# Buzzer_Box.net
KiCad netlist of a schematic drawn in EAGLE
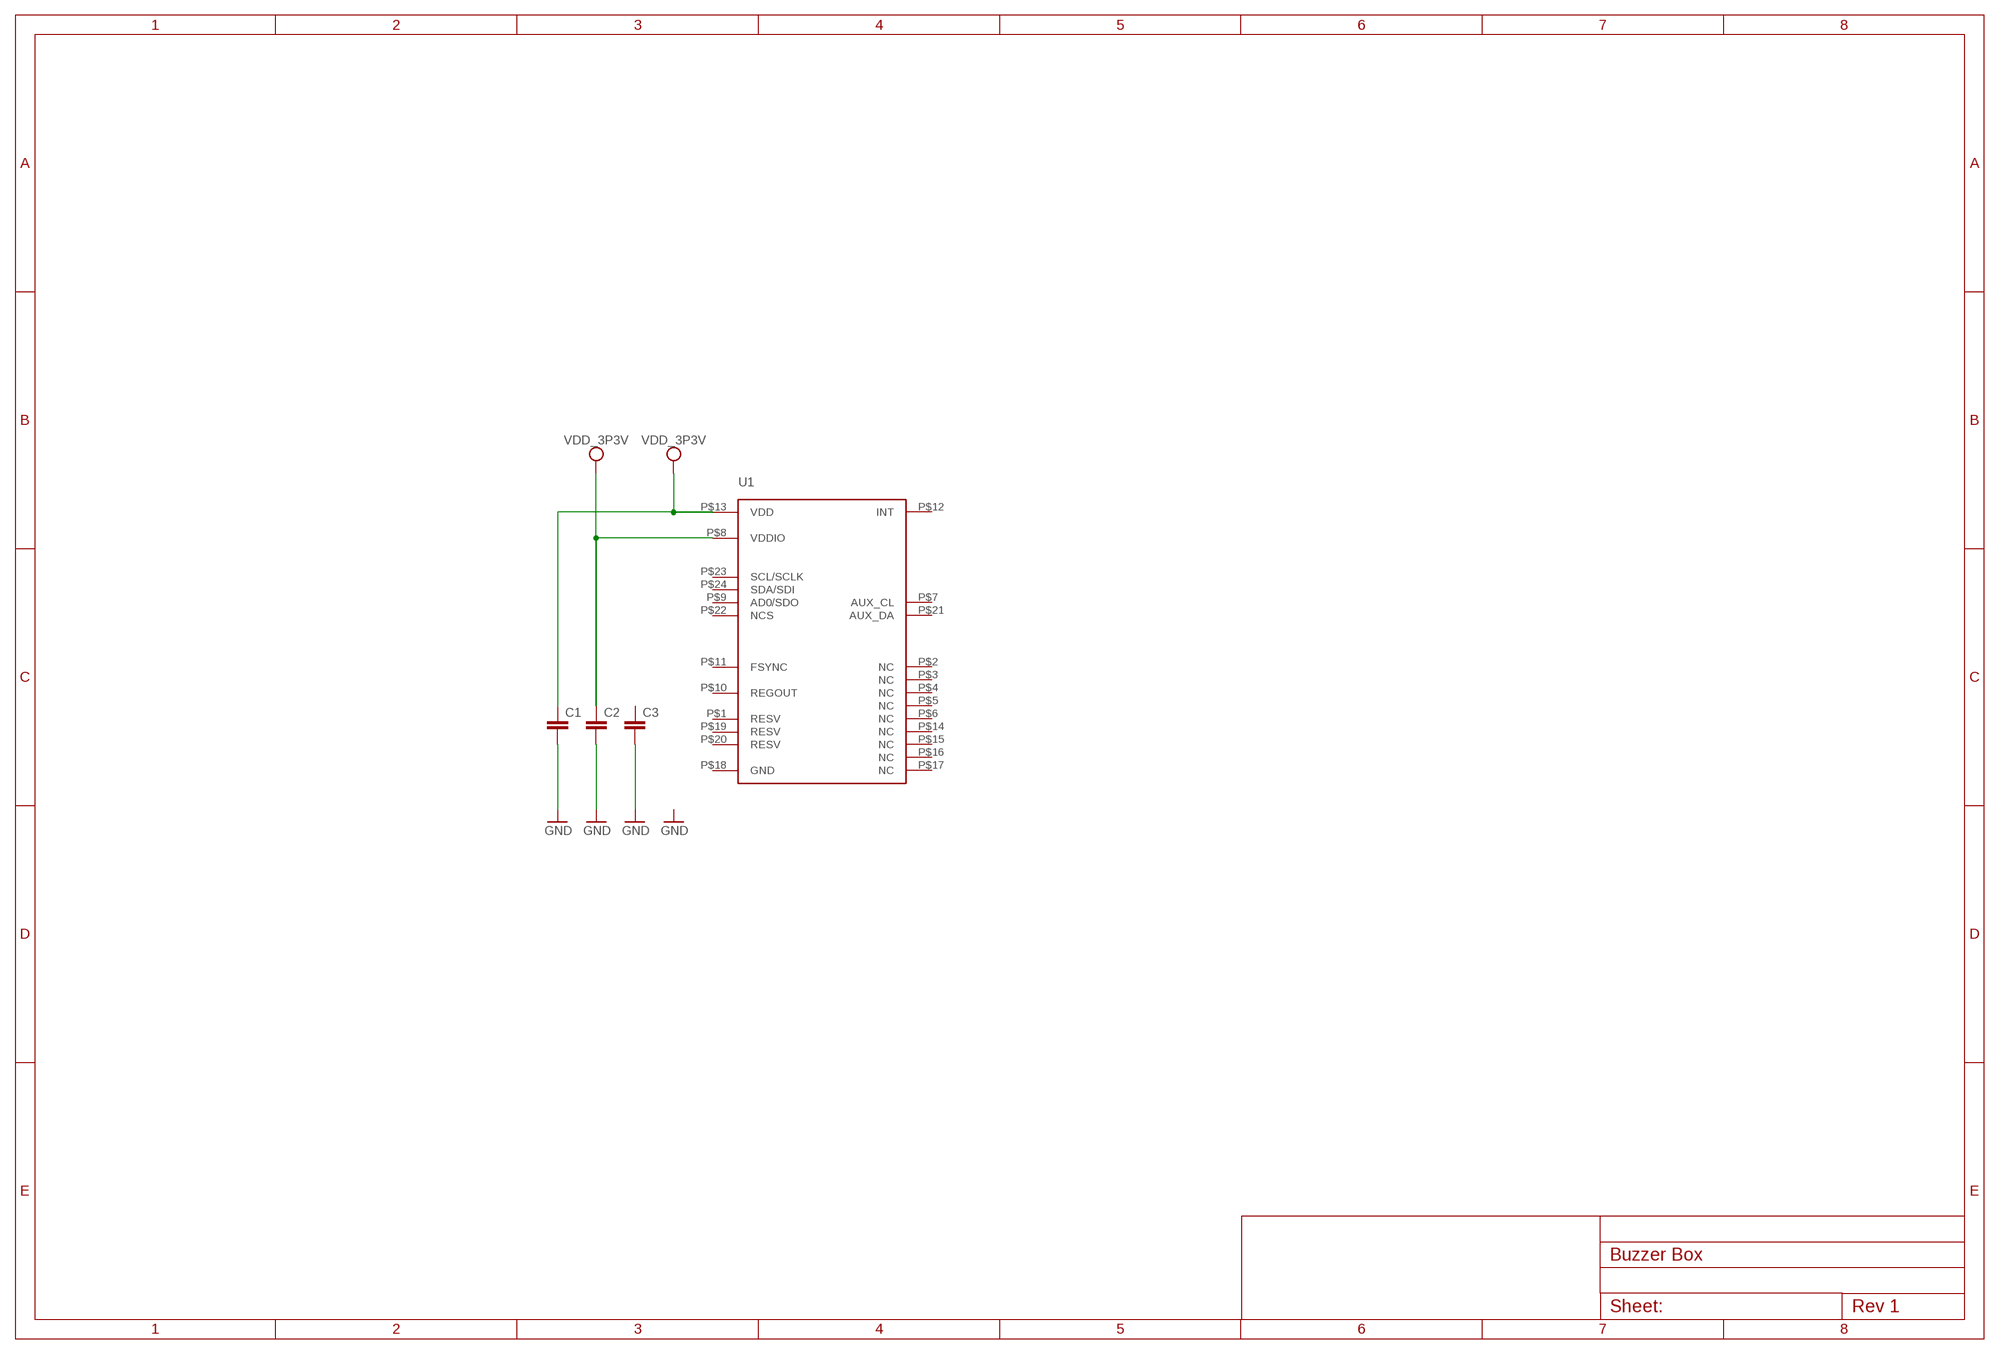
[diagram p0: schematic, sheet 1]

(export (version "E")
  (design (tool "Eeschema 10.0.6"))
  (components
    (comp (ref "C1")
      (value "C_C0402")
      (footprint "eagle-import:C0402")
      (libsource (lib "eagle-import") (part "C_C0402"))
    )
    (comp (ref "C2")
      (value "C_C0402")
      (footprint "eagle-import:C0402")
      (libsource (lib "eagle-import") (part "C_C0402"))
    )
    (comp (ref "C3")
      (value "C_C0402")
      (footprint "eagle-import:C0402")
      (libsource (lib "eagle-import") (part "C_C0402"))
    )
    (comp (ref "U1")
      (value "MPU-9250")
      (footprint "eagle-import:QFN-3X3MM")
      (libsource (lib "eagle-import") (part "MPU-9250"))
    )
  )
  (nets
    (net (code "1") (name "GND") (class "Default")
      (node (ref "C1") (pin "2") (pinfunction "2_2") (pintype "passive"))
      (node (ref "C2") (pin "2") (pinfunction "2_2") (pintype "passive"))
      (node (ref "C3") (pin "2") (pinfunction "2_2") (pintype "passive"))
    )
    (net (code "2") (name "VDD_3P3V") (class "Default")
      (node (ref "C1") (pin "1") (pinfunction "1_1") (pintype "passive"))
      (node (ref "C2") (pin "1") (pinfunction "1_1") (pintype "passive"))
      (node (ref "U1") (pin "P$13") (pinfunction "VDD_P$13") (pintype "bidirectional"))
      (node (ref "U1") (pin "P$8") (pinfunction "VDDIO_P$8") (pintype "bidirectional"))
    )
    (net (code "3") (name "unconnected-(C3-Pad1)") (class "Default")
      (node (ref "C3") (pin "1") (pinfunction "1_1") (pintype "passive"))
    )
    (net (code "4") (name "unconnected-(U1-AD0{slash}SDO-PadP$9)") (class "Default")
      (node (ref "U1") (pin "P$9") (pinfunction "AD0/SDO_P$9") (pintype "bidirectional"))
    )
    (net (code "5") (name "unconnected-(U1-AUX_CL-PadP$7)") (class "Default")
      (node (ref "U1") (pin "P$7") (pinfunction "AUX_CL_P$7") (pintype "bidirectional"))
    )
    (net (code "6") (name "unconnected-(U1-AUX_DA-PadP$21)") (class "Default")
      (node (ref "U1") (pin "P$21") (pinfunction "AUX_DA_P$21") (pintype "bidirectional"))
    )
    (net (code "7") (name "unconnected-(U1-FSYNC-PadP$11)") (class "Default")
      (node (ref "U1") (pin "P$11") (pinfunction "FSYNC_P$11") (pintype "bidirectional"))
    )
    (net (code "8") (name "unconnected-(U1-GND-PadP$18)") (class "Default")
      (node (ref "U1") (pin "P$18") (pinfunction "GND_P$18") (pintype "bidirectional"))
    )
    (net (code "9") (name "unconnected-(U1-INT-PadP$12)") (class "Default")
      (node (ref "U1") (pin "P$12") (pinfunction "INT_P$12") (pintype "bidirectional"))
    )
    (net (code "10") (name "unconnected-(U1-NC-PadP$2)") (class "Default")
      (node (ref "U1") (pin "P$2") (pinfunction "NC_P$2") (pintype "bidirectional"))
    )
    (net (code "11") (name "unconnected-(U1-NC-PadP$3)") (class "Default")
      (node (ref "U1") (pin "P$3") (pinfunction "NC_P$3") (pintype "bidirectional"))
    )
    (net (code "12") (name "unconnected-(U1-NC-PadP$4)") (class "Default")
      (node (ref "U1") (pin "P$4") (pinfunction "NC_P$4") (pintype "bidirectional"))
    )
    (net (code "13") (name "unconnected-(U1-NC-PadP$5)") (class "Default")
      (node (ref "U1") (pin "P$5") (pinfunction "NC_P$5") (pintype "bidirectional"))
    )
    (net (code "14") (name "unconnected-(U1-NC-PadP$6)") (class "Default")
      (node (ref "U1") (pin "P$6") (pinfunction "NC_P$6") (pintype "bidirectional"))
    )
    (net (code "15") (name "unconnected-(U1-NC-PadP$14)") (class "Default")
      (node (ref "U1") (pin "P$14") (pinfunction "NC_P$14") (pintype "bidirectional"))
    )
    (net (code "16") (name "unconnected-(U1-NC-PadP$15)") (class "Default")
      (node (ref "U1") (pin "P$15") (pinfunction "NC_P$15") (pintype "bidirectional"))
    )
    (net (code "17") (name "unconnected-(U1-NC-PadP$16)") (class "Default")
      (node (ref "U1") (pin "P$16") (pinfunction "NC_P$16") (pintype "bidirectional"))
    )
    (net (code "18") (name "unconnected-(U1-NC-PadP$17)") (class "Default")
      (node (ref "U1") (pin "P$17") (pinfunction "NC_P$17") (pintype "bidirectional"))
    )
    (net (code "19") (name "unconnected-(U1-NCS-PadP$22)") (class "Default")
      (node (ref "U1") (pin "P$22") (pinfunction "NCS_P$22") (pintype "bidirectional"))
    )
    (net (code "20") (name "unconnected-(U1-REGOUT-PadP$10)") (class "Default")
      (node (ref "U1") (pin "P$10") (pinfunction "REGOUT_P$10") (pintype "bidirectional"))
    )
    (net (code "21") (name "unconnected-(U1-RESV-PadP$1)") (class "Default")
      (node (ref "U1") (pin "P$1") (pinfunction "RESV_P$1") (pintype "bidirectional"))
    )
    (net (code "22") (name "unconnected-(U1-RESV-PadP$19)") (class "Default")
      (node (ref "U1") (pin "P$19") (pinfunction "RESV_P$19") (pintype "bidirectional"))
    )
    (net (code "23") (name "unconnected-(U1-RESV-PadP$20)") (class "Default")
      (node (ref "U1") (pin "P$20") (pinfunction "RESV_P$20") (pintype "bidirectional"))
    )
    (net (code "24") (name "unconnected-(U1-SCL{slash}SCLK-PadP$23)") (class "Default")
      (node (ref "U1") (pin "P$23") (pinfunction "SCL/SCLK_P$23") (pintype "bidirectional"))
    )
    (net (code "25") (name "unconnected-(U1-SDA{slash}SDI-PadP$24)") (class "Default")
      (node (ref "U1") (pin "P$24") (pinfunction "SDA/SDI_P$24") (pintype "bidirectional"))
    )
  )
)
